# 10_-_ESP32.net
KiCad netlist of a schematic drawn in Altium Designer
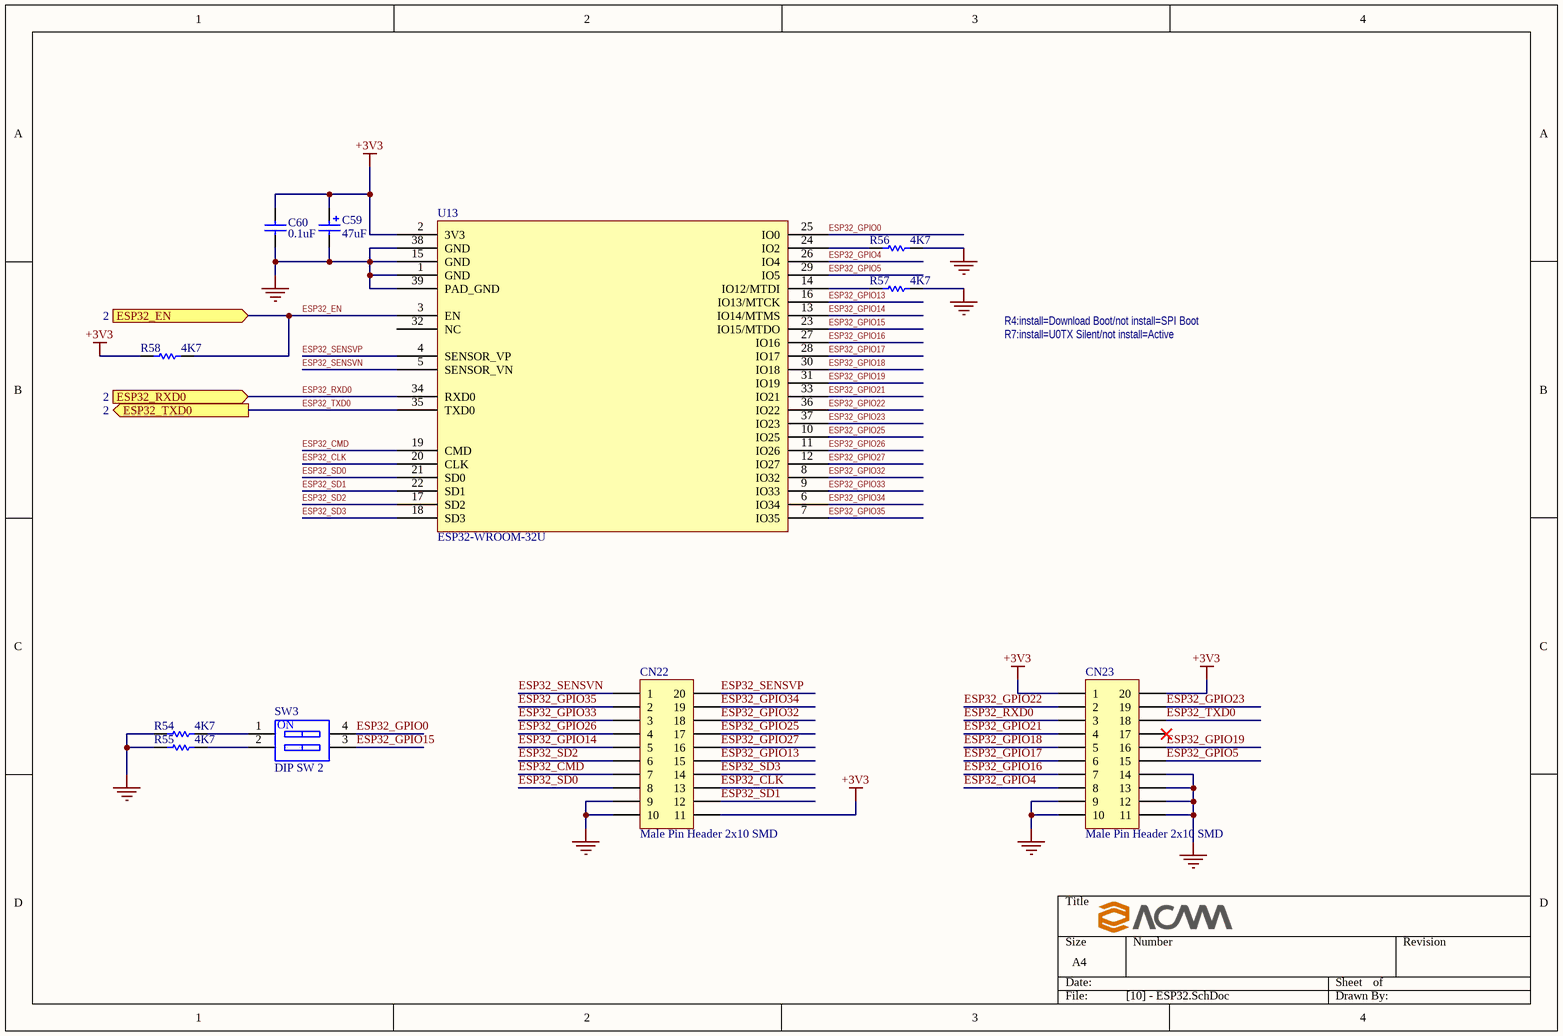
[diagram p0: [10] - ESP32.SchDoc]

(export (version "E")
  (design (tool "Eeschema 10.0.6"))
  (components
    (comp (ref "C59")
      (value "47uF")
      (footprint "TANT_B")
      (description "Tantalum Polarized Capacitor")
      (libsource (lib "Farzan Custom Library") (part "Cap Tant"))
    )
    (comp (ref "C60")
      (value "0.1uF")
      (footprint "0402_C")
      (description "Non-Pol SMD Capacitor")
      (libsource (lib "Farzan Custom Library") (part "Cap SMD"))
    )
    (comp (ref "CN22")
      (value "Male Pin Header 2x10 SMD")
      (footprint "HEADER_SMD_2x10")
      (description "SMD Male Pin Header 2.54mm Pitch, 2x10")
      (libsource (lib "Farzan Custom Library") (part "Pin header Male 2x10 smd"))
    )
    (comp (ref "CN23")
      (value "Male Pin Header 2x10 SMD")
      (footprint "HEADER_SMD_2x10")
      (description "SMD Male Pin Header 2.54mm Pitch, 2x10")
      (libsource (lib "Farzan Custom Library") (part "Pin header Male 2x10 smd"))
    )
    (comp (ref "R54")
      (value "4K7")
      (footprint "0402_R")
      (description "SMD Resistor")
      (fields (field (name "TOLERANCE") "1%"))
      (libsource (lib "Farzan Custom Library") (part "Res SMD"))
    )
    (comp (ref "R55")
      (value "4K7")
      (footprint "0402_R")
      (description "SMD Resistor")
      (fields (field (name "TOLERANCE") "1%"))
      (libsource (lib "Farzan Custom Library") (part "Res SMD"))
    )
    (comp (ref "R56")
      (value "4K7")
      (footprint "0402_R")
      (description "SMD Resistor")
      (fields (field (name "TOLERANCE") "1%"))
      (libsource (lib "Farzan Custom Library") (part "Res SMD"))
    )
    (comp (ref "R57")
      (value "4K7")
      (footprint "0402_R")
      (description "SMD Resistor")
      (fields (field (name "TOLERANCE") "1%"))
      (libsource (lib "Farzan Custom Library") (part "Res SMD"))
    )
    (comp (ref "R58")
      (value "4K7")
      (footprint "0402_R")
      (description "SMD Resistor")
      (fields (field (name "TOLERANCE") "1%"))
      (libsource (lib "Farzan Custom Library") (part "Res SMD"))
    )
    (comp (ref "SW3")
      (value "DIP SW 2")
      (footprint "DIP-SW-2-Piano")
      (description "DIP Switch, 2 Position, SPST")
      (fields (field (name "MANUFACTURER PART NUM") "BPA02B"))
      (libsource (lib "Farzan Custom Library") (part "DIP SW-2"))
    )
    (comp (ref "U13")
      (value "ESP32-WROOM-32U")
      (footprint "ESP32S_W")
      (description "powerful, generic Wi-Fi+BT+BLE MCU module")
      (libsource (lib "Farzan Custom Library") (part "ESP32-WROOM-32U"))
    )
  )
  (nets
    (net (code "1") (name "+3V3") (class "Default")
      (node (ref "C59") (pin "1") (pinfunction "1_1") (pintype "passive"))
      (node (ref "C60") (pin "1") (pinfunction "1_1") (pintype "passive"))
      (node (ref "CN22") (pin "11") (pinfunction "11_11") (pintype "passive"))
      (node (ref "CN23") (pin "1") (pinfunction "1_1") (pintype "passive"))
      (node (ref "CN23") (pin "20") (pinfunction "20_20") (pintype "passive"))
      (node (ref "R58") (pin "1") (pinfunction "1_1") (pintype "passive"))
      (node (ref "U13") (pin "2") (pinfunction "3V3_2") (pintype "power_in"))
    )
    (net (code "2") (name "/ESP32_CLK") (class "Default")
      (node (ref "CN22") (pin "13") (pinfunction "13_13") (pintype "passive"))
      (node (ref "U13") (pin "20") (pinfunction "CLK_20") (pintype "passive"))
    )
    (net (code "3") (name "/ESP32_CMD") (class "Default")
      (node (ref "CN22") (pin "7") (pinfunction "7_7") (pintype "passive"))
      (node (ref "U13") (pin "19") (pinfunction "CMD_19") (pintype "passive"))
    )
    (net (code "4") (name "/ESP32_EN") (class "Default")
      (node (ref "R58") (pin "2") (pinfunction "2_2") (pintype "passive"))
      (node (ref "U13") (pin "3") (pinfunction "EN_3") (pintype "passive"))
    )
    (net (code "5") (name "/ESP32_GPIO0") (class "Default")
      (node (ref "SW3") (pin "4") (pinfunction "A4_4") (pintype "passive"))
      (node (ref "U13") (pin "25") (pinfunction "IO0_25") (pintype "passive"))
    )
    (net (code "6") (name "/ESP32_GPIO4") (class "Default")
      (node (ref "CN23") (pin "8") (pinfunction "8_8") (pintype "passive"))
      (node (ref "U13") (pin "26") (pinfunction "IO4_26") (pintype "passive"))
    )
    (net (code "7") (name "/ESP32_GPIO5") (class "Default")
      (node (ref "CN23") (pin "15") (pinfunction "15_15") (pintype "passive"))
      (node (ref "U13") (pin "29") (pinfunction "IO5_29") (pintype "passive"))
    )
    (net (code "8") (name "/ESP32_GPIO13") (class "Default")
      (node (ref "CN22") (pin "15") (pinfunction "15_15") (pintype "passive"))
      (node (ref "U13") (pin "16") (pinfunction "IO13/MTCK_16") (pintype "passive"))
    )
    (net (code "9") (name "/ESP32_GPIO14") (class "Default")
      (node (ref "CN22") (pin "5") (pinfunction "5_5") (pintype "passive"))
      (node (ref "U13") (pin "13") (pinfunction "IO14/MTMS_13") (pintype "passive"))
    )
    (net (code "10") (name "/ESP32_GPIO15") (class "Default")
      (node (ref "SW3") (pin "3") (pinfunction "A3_3") (pintype "passive"))
      (node (ref "U13") (pin "23") (pinfunction "IO15/MTDO_23") (pintype "passive"))
    )
    (net (code "11") (name "/ESP32_GPIO16") (class "Default")
      (node (ref "CN23") (pin "7") (pinfunction "7_7") (pintype "passive"))
      (node (ref "U13") (pin "27") (pinfunction "IO16_27") (pintype "passive"))
    )
    (net (code "12") (name "/ESP32_GPIO17") (class "Default")
      (node (ref "CN23") (pin "6") (pinfunction "6_6") (pintype "passive"))
      (node (ref "U13") (pin "28") (pinfunction "IO17_28") (pintype "passive"))
    )
    (net (code "13") (name "/ESP32_GPIO18") (class "Default")
      (node (ref "CN23") (pin "5") (pinfunction "5_5") (pintype "passive"))
      (node (ref "U13") (pin "30") (pinfunction "IO18_30") (pintype "passive"))
    )
    (net (code "14") (name "/ESP32_GPIO19") (class "Default")
      (node (ref "CN23") (pin "16") (pinfunction "16_16") (pintype "passive"))
      (node (ref "U13") (pin "31") (pinfunction "IO19_31") (pintype "passive"))
    )
    (net (code "15") (name "/ESP32_GPIO21") (class "Default")
      (node (ref "CN23") (pin "4") (pinfunction "4_4") (pintype "passive"))
      (node (ref "U13") (pin "33") (pinfunction "IO21_33") (pintype "passive"))
    )
    (net (code "16") (name "/ESP32_GPIO22") (class "Default")
      (node (ref "CN23") (pin "2") (pinfunction "2_2") (pintype "passive"))
      (node (ref "U13") (pin "36") (pinfunction "IO22_36") (pintype "passive"))
    )
    (net (code "17") (name "/ESP32_GPIO23") (class "Default")
      (node (ref "CN23") (pin "19") (pinfunction "19_19") (pintype "passive"))
      (node (ref "U13") (pin "37") (pinfunction "IO23_37") (pintype "passive"))
    )
    (net (code "18") (name "/ESP32_GPIO25") (class "Default")
      (node (ref "CN22") (pin "17") (pinfunction "17_17") (pintype "passive"))
      (node (ref "U13") (pin "10") (pinfunction "IO25_10") (pintype "passive"))
    )
    (net (code "19") (name "/ESP32_GPIO26") (class "Default")
      (node (ref "CN22") (pin "4") (pinfunction "4_4") (pintype "passive"))
      (node (ref "U13") (pin "11") (pinfunction "IO26_11") (pintype "passive"))
    )
    (net (code "20") (name "/ESP32_GPIO27") (class "Default")
      (node (ref "CN22") (pin "16") (pinfunction "16_16") (pintype "passive"))
      (node (ref "U13") (pin "12") (pinfunction "IO27_12") (pintype "passive"))
    )
    (net (code "21") (name "/ESP32_GPIO32") (class "Default")
      (node (ref "CN22") (pin "18") (pinfunction "18_18") (pintype "passive"))
      (node (ref "U13") (pin "8") (pinfunction "IO32_8") (pintype "passive"))
    )
    (net (code "22") (name "/ESP32_GPIO33") (class "Default")
      (node (ref "CN22") (pin "3") (pinfunction "3_3") (pintype "passive"))
      (node (ref "U13") (pin "9") (pinfunction "IO33_9") (pintype "passive"))
    )
    (net (code "23") (name "/ESP32_GPIO34") (class "Default")
      (node (ref "CN22") (pin "19") (pinfunction "19_19") (pintype "passive"))
      (node (ref "U13") (pin "6") (pinfunction "IO34_6") (pintype "passive"))
    )
    (net (code "24") (name "/ESP32_GPIO35") (class "Default")
      (node (ref "CN22") (pin "2") (pinfunction "2_2") (pintype "passive"))
      (node (ref "U13") (pin "7") (pinfunction "IO35_7") (pintype "passive"))
    )
    (net (code "25") (name "/ESP32_RXD0") (class "Default")
      (node (ref "CN23") (pin "3") (pinfunction "3_3") (pintype "passive"))
      (node (ref "U13") (pin "34") (pinfunction "RXD0_34") (pintype "passive"))
    )
    (net (code "26") (name "/ESP32_SD0") (class "Default")
      (node (ref "CN22") (pin "8") (pinfunction "8_8") (pintype "passive"))
      (node (ref "U13") (pin "21") (pinfunction "SD0_21") (pintype "passive"))
    )
    (net (code "27") (name "/ESP32_SD1") (class "Default")
      (node (ref "CN22") (pin "12") (pinfunction "12_12") (pintype "passive"))
      (node (ref "U13") (pin "22") (pinfunction "SD1_22") (pintype "passive"))
    )
    (net (code "28") (name "/ESP32_SD2") (class "Default")
      (node (ref "CN22") (pin "6") (pinfunction "6_6") (pintype "passive"))
      (node (ref "U13") (pin "17") (pinfunction "SD2_17") (pintype "passive"))
    )
    (net (code "29") (name "/ESP32_SD3") (class "Default")
      (node (ref "CN22") (pin "14") (pinfunction "14_14") (pintype "passive"))
      (node (ref "U13") (pin "18") (pinfunction "SD3_18") (pintype "passive"))
    )
    (net (code "30") (name "/ESP32_SENSVN") (class "Default")
      (node (ref "CN22") (pin "1") (pinfunction "1_1") (pintype "passive"))
      (node (ref "U13") (pin "5") (pinfunction "SENSOR_VN_5") (pintype "passive"))
    )
    (net (code "31") (name "/ESP32_SENSVP") (class "Default")
      (node (ref "CN22") (pin "20") (pinfunction "20_20") (pintype "passive"))
      (node (ref "U13") (pin "4") (pinfunction "SENSOR_VP_4") (pintype "passive"))
    )
    (net (code "32") (name "/ESP32_TXD0") (class "Default")
      (node (ref "CN23") (pin "18") (pinfunction "18_18") (pintype "passive"))
      (node (ref "U13") (pin "35") (pinfunction "TXD0_35") (pintype "passive"))
    )
    (net (code "33") (name "GND") (class "Default")
      (node (ref "C59") (pin "2") (pinfunction "2_2") (pintype "passive"))
      (node (ref "C60") (pin "2") (pinfunction "2_2") (pintype "passive"))
      (node (ref "CN22") (pin "10") (pinfunction "10_10") (pintype "passive"))
      (node (ref "CN22") (pin "9") (pinfunction "9_9") (pintype "passive"))
      (node (ref "CN23") (pin "10") (pinfunction "10_10") (pintype "passive"))
      (node (ref "CN23") (pin "11") (pinfunction "11_11") (pintype "passive"))
      (node (ref "CN23") (pin "12") (pinfunction "12_12") (pintype "passive"))
      (node (ref "CN23") (pin "13") (pinfunction "13_13") (pintype "passive"))
      (node (ref "CN23") (pin "14") (pinfunction "14_14") (pintype "passive"))
      (node (ref "CN23") (pin "9") (pinfunction "9_9") (pintype "passive"))
      (node (ref "R54") (pin "1") (pinfunction "1_1") (pintype "passive"))
      (node (ref "R55") (pin "1") (pinfunction "1_1") (pintype "passive"))
      (node (ref "R56") (pin "2") (pinfunction "2_2") (pintype "passive"))
      (node (ref "R57") (pin "2") (pinfunction "2_2") (pintype "passive"))
      (node (ref "U13") (pin "1") (pinfunction "GND_1") (pintype "power_in"))
      (node (ref "U13") (pin "15") (pinfunction "GND_15") (pintype "power_in"))
      (node (ref "U13") (pin "38") (pinfunction "GND_38") (pintype "power_in"))
      (node (ref "U13") (pin "39") (pinfunction "PAD_GND_39") (pintype "passive"))
    )
    (net (code "34") (name "Net-(SW3-A1)") (class "Default")
      (node (ref "R54") (pin "2") (pinfunction "2_2") (pintype "passive"))
      (node (ref "SW3") (pin "1") (pinfunction "A1_1") (pintype "passive"))
    )
    (net (code "35") (name "Net-(SW3-A2)") (class "Default")
      (node (ref "R55") (pin "2") (pinfunction "2_2") (pintype "passive"))
      (node (ref "SW3") (pin "2") (pinfunction "A2_2") (pintype "passive"))
    )
    (net (code "36") (name "Net-(U13-IO2)") (class "Default")
      (node (ref "R56") (pin "1") (pinfunction "1_1") (pintype "passive"))
      (node (ref "U13") (pin "24") (pinfunction "IO2_24") (pintype "passive"))
    )
    (net (code "37") (name "Net-(U13-IO12{slash}MTDI)") (class "Default")
      (node (ref "R57") (pin "1") (pinfunction "1_1") (pintype "passive"))
      (node (ref "U13") (pin "14") (pinfunction "IO12/MTDI_14") (pintype "passive"))
    )
    (net (code "38") (name "unconnected-(CN23-Pad17)") (class "Default")
      (node (ref "CN23") (pin "17") (pinfunction "17_17") (pintype "passive+no_connect"))
    )
    (net (code "39") (name "unconnected-(U13-NC-Pad32)") (class "Default")
      (node (ref "U13") (pin "32") (pinfunction "NC_32") (pintype "passive"))
    )
  )
)
